# Filter.net
KiCad netlist of a schematic drawn in EAGLE
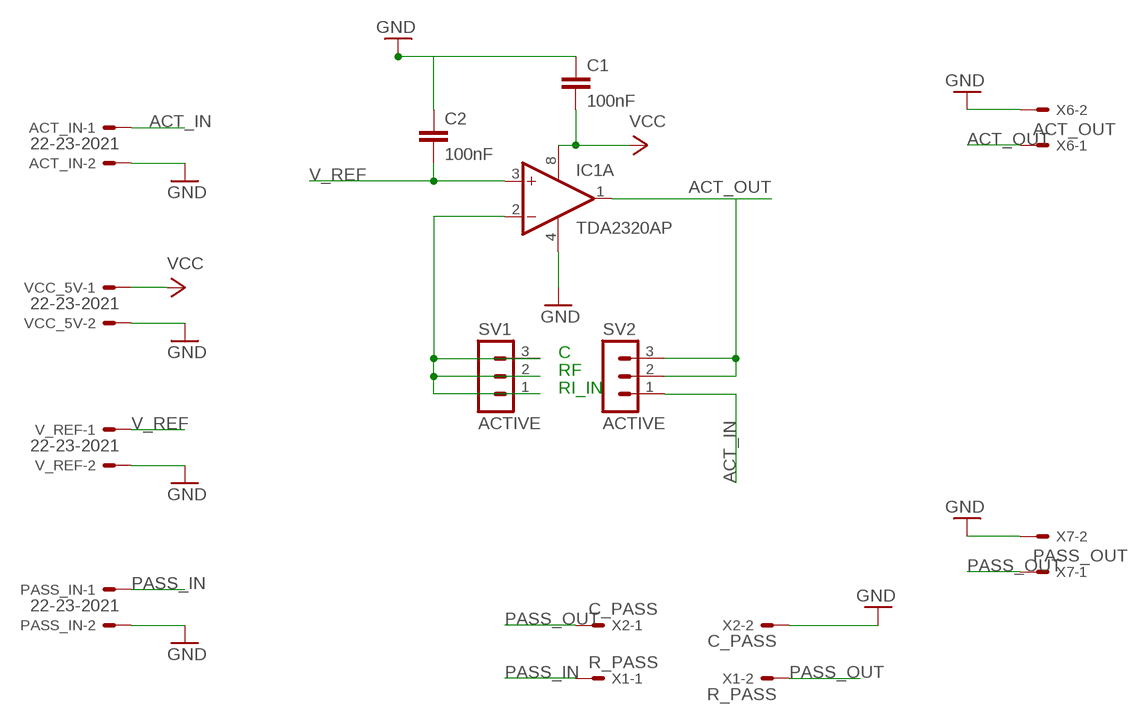
[diagram p0: schematic, sheet 1]

(export (version "E")
  (design (tool "Eeschema 10.0.6"))
  (components
    (comp (ref "ACT_IN")
      (value "22-23-2021")
      (footprint "eagle-import:22-23-2021")
      (fields (field (name "MF") "MOLEX"))
      (libsource (lib "eagle-import") (part "22-23-2021"))
    )
    (comp (ref "C1")
      (value "100nF")
      (footprint "eagle-import:C5B3")
      (libsource (lib "eagle-import") (part "C5/3"))
    )
    (comp (ref "C2")
      (value "100nF")
      (footprint "eagle-import:C5B3")
      (libsource (lib "eagle-import") (part "C5/3"))
    )
    (comp (ref "IC1")
      (value "TDA2320AP")
      (footprint "eagle-import:DIL08")
      (libsource (lib "eagle-import") (part "TDA2320AP"))
    )
    (comp (ref "PASS_IN")
      (value "22-23-2021")
      (footprint "eagle-import:22-23-2021")
      (fields (field (name "MF") "MOLEX"))
      (libsource (lib "eagle-import") (part "22-23-2021"))
    )
    (comp (ref "SV1")
      (value "ACTIVE")
      (footprint "eagle-import:MA03-1")
      (libsource (lib "eagle-import") (part "MA03-1"))
    )
    (comp (ref "SV2")
      (value "ACTIVE")
      (footprint "eagle-import:MA03-1")
      (libsource (lib "eagle-import") (part "MA03-1"))
    )
    (comp (ref "VCC_5V")
      (value "22-23-2021")
      (footprint "eagle-import:22-23-2021")
      (fields (field (name "MF") "MOLEX"))
      (libsource (lib "eagle-import") (part "22-23-2021"))
    )
    (comp (ref "V_REF")
      (value "22-23-2021")
      (footprint "eagle-import:22-23-2021")
      (fields (field (name "MF") "MOLEX"))
      (libsource (lib "eagle-import") (part "22-23-2021"))
    )
    (comp (ref "X1")
      (value "R_PASS")
      (footprint "eagle-import:87758-0216")
      (fields (field (name "MPN") "87758-0216"))
      (libsource (lib "eagle-import") (part "87758-0216"))
    )
    (comp (ref "X2")
      (value "C_PASS")
      (footprint "eagle-import:87758-0216")
      (fields (field (name "MPN") "87758-0216"))
      (libsource (lib "eagle-import") (part "87758-0216"))
    )
    (comp (ref "X6")
      (value "ACT_OUT")
      (footprint "eagle-import:22-23-2021")
      (fields (field (name "MF") "MOLEX") (field (name "MPN") "22-23-2021"))
      (libsource (lib "eagle-import") (part "22-23-2021"))
    )
    (comp (ref "X7")
      (value "PASS_OUT")
      (footprint "eagle-import:22-23-2021")
      (fields (field (name "MF") "MOLEX") (field (name "MPN") "22-23-2021"))
      (libsource (lib "eagle-import") (part "22-23-2021"))
    )
  )
  (nets
    (net (code "1") (name "/ACT_IN") (class "Default")
      (node (ref "ACT_IN") (pin "1") (pinfunction "S_1") (pintype "passive"))
      (node (ref "SV2") (pin "1") (pinfunction "1_1") (pintype "passive"))
    )
    (net (code "2") (name "/ACT_OUT") (class "Default")
      (node (ref "IC1") (pin "1") (pinfunction "OUT_1") (pintype "output"))
      (node (ref "SV2") (pin "2") (pinfunction "2_2") (pintype "passive"))
      (node (ref "SV2") (pin "3") (pinfunction "3_3") (pintype "passive"))
      (node (ref "X6") (pin "1") (pinfunction "S_1") (pintype "passive"))
    )
    (net (code "3") (name "/PASS_IN") (class "Default")
      (node (ref "PASS_IN") (pin "1") (pinfunction "S_1") (pintype "passive"))
      (node (ref "X1") (pin "1") (pinfunction "S_1") (pintype "passive"))
    )
    (net (code "4") (name "/PASS_OUT") (class "Default")
      (node (ref "X1") (pin "2") (pinfunction "S_2") (pintype "passive"))
      (node (ref "X2") (pin "1") (pinfunction "S_1") (pintype "passive"))
      (node (ref "X7") (pin "1") (pinfunction "S_1") (pintype "passive"))
    )
    (net (code "5") (name "/V_REF") (class "Default")
      (node (ref "C2") (pin "2") (pinfunction "2_2") (pintype "passive"))
      (node (ref "IC1") (pin "3") (pinfunction "+IN_3") (pintype "input"))
      (node (ref "V_REF") (pin "1") (pinfunction "S_1") (pintype "passive"))
    )
    (net (code "6") (name "GND") (class "Default")
      (node (ref "ACT_IN") (pin "2") (pinfunction "S_2") (pintype "passive"))
      (node (ref "C1") (pin "1") (pinfunction "1_1") (pintype "passive"))
      (node (ref "C2") (pin "1") (pinfunction "1_1") (pintype "passive"))
      (node (ref "IC1") (pin "4") (pinfunction "V-_4") (pintype "power_in"))
      (node (ref "PASS_IN") (pin "2") (pinfunction "S_2") (pintype "passive"))
      (node (ref "VCC_5V") (pin "2") (pinfunction "S_2") (pintype "passive"))
      (node (ref "V_REF") (pin "2") (pinfunction "S_2") (pintype "passive"))
      (node (ref "X2") (pin "2") (pinfunction "S_2") (pintype "passive"))
      (node (ref "X6") (pin "2") (pinfunction "S_2") (pintype "passive"))
      (node (ref "X7") (pin "2") (pinfunction "S_2") (pintype "passive"))
    )
    (net (code "7") (name "Net-(IC1A--IN)") (class "Default")
      (node (ref "IC1") (pin "2") (pinfunction "-IN_2") (pintype "input"))
      (node (ref "SV1") (pin "1") (pinfunction "1_1") (pintype "passive"))
      (node (ref "SV1") (pin "2") (pinfunction "2_2") (pintype "passive"))
      (node (ref "SV1") (pin "3") (pinfunction "3_3") (pintype "passive"))
    )
    (net (code "8") (name "VCC") (class "Default")
      (node (ref "C1") (pin "2") (pinfunction "2_2") (pintype "passive"))
      (node (ref "IC1") (pin "8") (pinfunction "V+_8") (pintype "power_in"))
      (node (ref "VCC_5V") (pin "1") (pinfunction "S_1") (pintype "passive"))
    )
  )
)
